# TIA_sep_amp_7_March.net
KiCad netlist of a schematic drawn in EAGLE
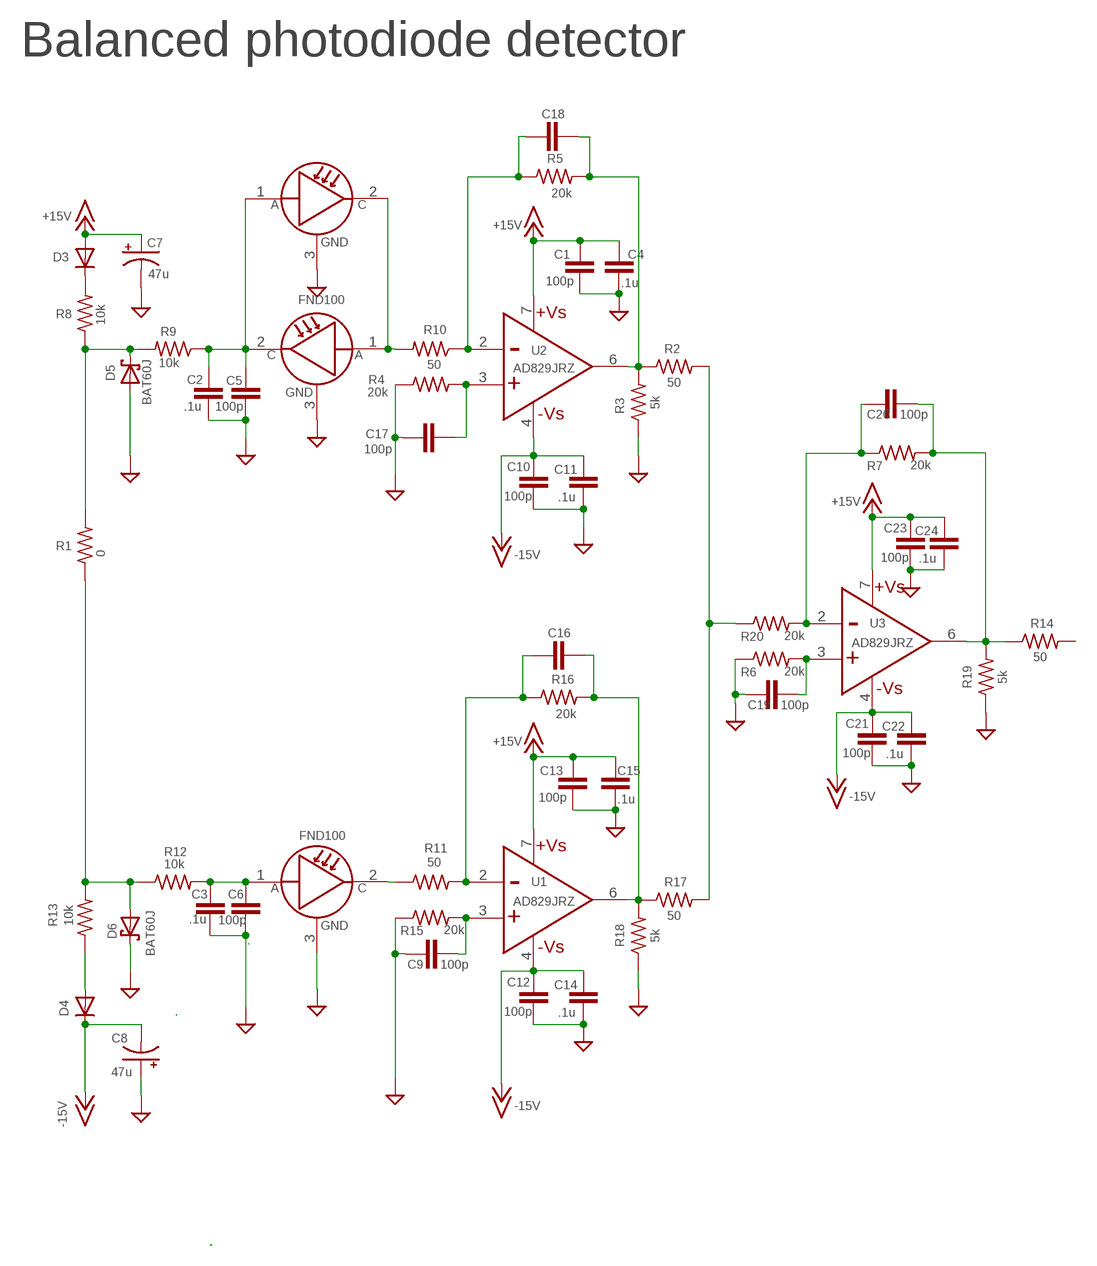
[diagram p0: schematic, sheet 1]

(export (version "E")
  (design (tool "Eeschema 10.0.6"))
  (components
    (comp (ref "C1")
      (value "100p")
      (footprint "eagle-import:C0603")
      (libsource (lib "eagle-import") (part "C-EUC0603"))
    )
    (comp (ref "C2")
      (value ".1u")
      (footprint "eagle-import:C0603")
      (libsource (lib "eagle-import") (part "C-EUC0603"))
    )
    (comp (ref "C3")
      (value ".1u")
      (footprint "eagle-import:C0603")
      (libsource (lib "eagle-import") (part "C-EUC0603"))
    )
    (comp (ref "C4")
      (value ".1u")
      (footprint "eagle-import:C0603")
      (libsource (lib "eagle-import") (part "C-EUC0603"))
    )
    (comp (ref "C5")
      (value "100p")
      (footprint "eagle-import:C0603")
      (libsource (lib "eagle-import") (part "C-EUC0603"))
    )
    (comp (ref "C6")
      (value "100p")
      (footprint "eagle-import:C0603")
      (libsource (lib "eagle-import") (part "C-EUC0603"))
    )
    (comp (ref "C7")
      (value "47u")
      (footprint "eagle-import:ETR3")
      (libsource (lib "eagle-import") (part "CPOL-USETR3"))
    )
    (comp (ref "C8")
      (value "47u")
      (footprint "eagle-import:ETR3")
      (libsource (lib "eagle-import") (part "CPOL-USETR3"))
    )
    (comp (ref "C9")
      (value "100p")
      (footprint "eagle-import:C0603")
      (libsource (lib "eagle-import") (part "C-EUC0603"))
    )
    (comp (ref "C10")
      (value "100p")
      (footprint "eagle-import:C0603")
      (libsource (lib "eagle-import") (part "C-EUC0603"))
    )
    (comp (ref "C11")
      (value ".1u")
      (footprint "eagle-import:C0603")
      (libsource (lib "eagle-import") (part "C-EUC0603"))
    )
    (comp (ref "C12")
      (value "100p")
      (footprint "eagle-import:C0603")
      (libsource (lib "eagle-import") (part "C-EUC0603"))
    )
    (comp (ref "C13")
      (value "100p")
      (footprint "eagle-import:C0603")
      (libsource (lib "eagle-import") (part "C-EUC0603"))
    )
    (comp (ref "C14")
      (value ".1u")
      (footprint "eagle-import:C0603")
      (libsource (lib "eagle-import") (part "C-EUC0603"))
    )
    (comp (ref "C15")
      (value ".1u")
      (footprint "eagle-import:C0603")
      (libsource (lib "eagle-import") (part "C-EUC0603"))
    )
    (comp (ref "C16")
      (value "C-EUC0603")
      (footprint "eagle-import:C0603")
      (libsource (lib "eagle-import") (part "C-EUC0603"))
    )
    (comp (ref "C17")
      (value "100p")
      (footprint "eagle-import:C0603")
      (libsource (lib "eagle-import") (part "C-EUC0603"))
    )
    (comp (ref "C18")
      (value "C-EUC0603")
      (footprint "eagle-import:C0603")
      (libsource (lib "eagle-import") (part "C-EUC0603"))
    )
    (comp (ref "C19")
      (value "100p")
      (footprint "eagle-import:C0603")
      (libsource (lib "eagle-import") (part "C-EUC0603"))
    )
    (comp (ref "C20")
      (value "100p")
      (footprint "eagle-import:C0603")
      (libsource (lib "eagle-import") (part "C-EUC0603"))
    )
    (comp (ref "C21")
      (value "100p")
      (footprint "eagle-import:C0603")
      (libsource (lib "eagle-import") (part "C-EUC0603"))
    )
    (comp (ref "C22")
      (value ".1u")
      (footprint "eagle-import:C0603")
      (libsource (lib "eagle-import") (part "C-EUC0603"))
    )
    (comp (ref "C23")
      (value "100p")
      (footprint "eagle-import:C0603")
      (libsource (lib "eagle-import") (part "C-EUC0603"))
    )
    (comp (ref "C24")
      (value ".1u")
      (footprint "eagle-import:C0603")
      (libsource (lib "eagle-import") (part "C-EUC0603"))
    )
    (comp (ref "D3")
      (value "SOD523DIODE")
      (footprint "eagle-import:SOD523")
      (libsource (lib "eagle-import") (part "SOD523DIODE"))
    )
    (comp (ref "D4")
      (value "SOD523DIODE")
      (footprint "eagle-import:SOD523")
      (libsource (lib "eagle-import") (part "SOD523DIODE"))
    )
    (comp (ref "D5")
      (value "BAT60J")
      (footprint "eagle-import:SOD323_ST")
      (libsource (lib "eagle-import") (part "BAT60J"))
    )
    (comp (ref "D6")
      (value "BAT60J")
      (footprint "eagle-import:SOD323_ST")
      (libsource (lib "eagle-import") (part "BAT60J"))
    )
    (comp (ref "R1")
      (value "0")
      (footprint "eagle-import:R0603")
      (libsource (lib "eagle-import") (part "R-US_R0603"))
    )
    (comp (ref "R2")
      (value "50")
      (footprint "eagle-import:R0603")
      (libsource (lib "eagle-import") (part "R-US_R0603"))
    )
    (comp (ref "R3")
      (value "5k")
      (footprint "eagle-import:R0603")
      (libsource (lib "eagle-import") (part "R-US_R0603"))
    )
    (comp (ref "R4")
      (value "20k")
      (footprint "eagle-import:R0603")
      (libsource (lib "eagle-import") (part "R-US_R0603"))
    )
    (comp (ref "R5")
      (value "20k")
      (footprint "eagle-import:R0603")
      (libsource (lib "eagle-import") (part "R-US_R0603"))
    )
    (comp (ref "R6")
      (value "20k")
      (footprint "eagle-import:R0603")
      (libsource (lib "eagle-import") (part "R-US_R0603"))
    )
    (comp (ref "R7")
      (value "20k")
      (footprint "eagle-import:R0603")
      (libsource (lib "eagle-import") (part "R-US_R0603"))
    )
    (comp (ref "R8")
      (value "10k")
      (footprint "eagle-import:R0603")
      (libsource (lib "eagle-import") (part "R-US_R0603"))
    )
    (comp (ref "R9")
      (value "10k")
      (footprint "eagle-import:R0603")
      (libsource (lib "eagle-import") (part "R-US_R0603"))
    )
    (comp (ref "R10")
      (value "50")
      (footprint "eagle-import:R0603")
      (libsource (lib "eagle-import") (part "R-US_R0603"))
    )
    (comp (ref "R11")
      (value "50")
      (footprint "eagle-import:R0603")
      (libsource (lib "eagle-import") (part "R-US_R0603"))
    )
    (comp (ref "R12")
      (value "10k")
      (footprint "eagle-import:R0603")
      (libsource (lib "eagle-import") (part "R-US_R0603"))
    )
    (comp (ref "R13")
      (value "10k")
      (footprint "eagle-import:R0603")
      (libsource (lib "eagle-import") (part "R-US_R0603"))
    )
    (comp (ref "R14")
      (value "50")
      (footprint "eagle-import:R0603")
      (libsource (lib "eagle-import") (part "R-US_R0603"))
    )
    (comp (ref "R15")
      (value "20k")
      (footprint "eagle-import:R0603")
      (libsource (lib "eagle-import") (part "R-US_R0603"))
    )
    (comp (ref "R16")
      (value "20k")
      (footprint "eagle-import:R0603")
      (libsource (lib "eagle-import") (part "R-US_R0603"))
    )
    (comp (ref "R17")
      (value "50")
      (footprint "eagle-import:R0603")
      (libsource (lib "eagle-import") (part "R-US_R0603"))
    )
    (comp (ref "R18")
      (value "5k")
      (footprint "eagle-import:R0603")
      (libsource (lib "eagle-import") (part "R-US_R0603"))
    )
    (comp (ref "R19")
      (value "5k")
      (footprint "eagle-import:R0603")
      (libsource (lib "eagle-import") (part "R-US_R0603"))
    )
    (comp (ref "R20")
      (value "20k")
      (footprint "eagle-import:R0603")
      (libsource (lib "eagle-import") (part "R-US_R0603"))
    )
    (comp (ref "U$1")
      (value "FND100")
      (footprint "eagle-import:TO254P939X470-3P")
      (libsource (lib "eagle-import") (part "FND100"))
    )
    (comp (ref "U$2")
      (value "FND100")
      (footprint "eagle-import:TO254P939X470-3P")
      (libsource (lib "eagle-import") (part "FND100"))
    )
    (comp (ref "U$4")
      (value "FND100")
      (footprint "eagle-import:TO254P939X470-3P")
      (libsource (lib "eagle-import") (part "FND100"))
    )
    (comp (ref "U1")
      (value "AD829JRZ")
      (footprint "eagle-import:SOIC127P600X175-8N")
      (libsource (lib "eagle-import") (part "AD829JRZ"))
    )
    (comp (ref "U2")
      (value "AD829JRZ")
      (footprint "eagle-import:SOIC127P600X175-8N")
      (libsource (lib "eagle-import") (part "AD829JRZ"))
    )
    (comp (ref "U3")
      (value "AD829JRZ")
      (footprint "eagle-import:SOIC127P600X175-8N")
      (libsource (lib "eagle-import") (part "AD829JRZ"))
    )
  )
  (nets
    (net (code "1") (name "+15V") (class "Default")
      (node (ref "C1") (pin "2") (pinfunction "2_2") (pintype "passive"))
      (node (ref "C13") (pin "2") (pinfunction "2_2") (pintype "passive"))
      (node (ref "C15") (pin "2") (pinfunction "2_2") (pintype "passive"))
      (node (ref "C23") (pin "2") (pinfunction "2_2") (pintype "passive"))
      (node (ref "C24") (pin "2") (pinfunction "2_2") (pintype "passive"))
      (node (ref "C4") (pin "2") (pinfunction "2_2") (pintype "passive"))
      (node (ref "C7") (pin "+") (pinfunction "+_+") (pintype "passive"))
      (node (ref "D3") (pin "A") (pinfunction "A_A") (pintype "passive"))
      (node (ref "U1") (pin "7") (pinfunction "+VS_7") (pintype "power_in"))
      (node (ref "U2") (pin "7") (pinfunction "+VS_7") (pintype "power_in"))
      (node (ref "U3") (pin "7") (pinfunction "+VS_7") (pintype "power_in"))
    )
    (net (code "2") (name "-15V") (class "Default")
      (node (ref "C10") (pin "2") (pinfunction "2_2") (pintype "passive"))
      (node (ref "C11") (pin "2") (pinfunction "2_2") (pintype "passive"))
      (node (ref "C12") (pin "2") (pinfunction "2_2") (pintype "passive"))
      (node (ref "C14") (pin "2") (pinfunction "2_2") (pintype "passive"))
      (node (ref "C21") (pin "2") (pinfunction "2_2") (pintype "passive"))
      (node (ref "C22") (pin "2") (pinfunction "2_2") (pintype "passive"))
      (node (ref "C8") (pin "-") (pinfunction "-_-") (pintype "passive"))
      (node (ref "D4") (pin "C") (pinfunction "C_C") (pintype "passive"))
      (node (ref "U1") (pin "4") (pinfunction "-VS_4") (pintype "power_in"))
      (node (ref "U2") (pin "4") (pinfunction "-VS_4") (pintype "power_in"))
      (node (ref "U3") (pin "4") (pinfunction "-VS_4") (pintype "power_in"))
    )
    (net (code "3") (name "GND") (class "Default")
      (node (ref "C1") (pin "1") (pinfunction "1_1") (pintype "passive"))
      (node (ref "C10") (pin "1") (pinfunction "1_1") (pintype "passive"))
      (node (ref "C11") (pin "1") (pinfunction "1_1") (pintype "passive"))
      (node (ref "C12") (pin "1") (pinfunction "1_1") (pintype "passive"))
      (node (ref "C13") (pin "1") (pinfunction "1_1") (pintype "passive"))
      (node (ref "C14") (pin "1") (pinfunction "1_1") (pintype "passive"))
      (node (ref "C15") (pin "1") (pinfunction "1_1") (pintype "passive"))
      (node (ref "C17") (pin "1") (pinfunction "1_1") (pintype "passive"))
      (node (ref "C19") (pin "1") (pinfunction "1_1") (pintype "passive"))
      (node (ref "C2") (pin "1") (pinfunction "1_1") (pintype "passive"))
      (node (ref "C21") (pin "1") (pinfunction "1_1") (pintype "passive"))
      (node (ref "C22") (pin "1") (pinfunction "1_1") (pintype "passive"))
      (node (ref "C23") (pin "1") (pinfunction "1_1") (pintype "passive"))
      (node (ref "C24") (pin "1") (pinfunction "1_1") (pintype "passive"))
      (node (ref "C3") (pin "1") (pinfunction "1_1") (pintype "passive"))
      (node (ref "C4") (pin "1") (pinfunction "1_1") (pintype "passive"))
      (node (ref "C5") (pin "1") (pinfunction "1_1") (pintype "passive"))
      (node (ref "C6") (pin "1") (pinfunction "1_1") (pintype "passive"))
      (node (ref "C7") (pin "-") (pinfunction "-_-") (pintype "passive"))
      (node (ref "C8") (pin "+") (pinfunction "+_+") (pintype "passive"))
      (node (ref "C9") (pin "1") (pinfunction "1_1") (pintype "passive"))
      (node (ref "D5") (pin "A") (pinfunction "A_A") (pintype "passive"))
      (node (ref "D6") (pin "C") (pinfunction "C_C") (pintype "passive"))
      (node (ref "R15") (pin "1") (pinfunction "1_1") (pintype "passive"))
      (node (ref "R18") (pin "1") (pinfunction "1_1") (pintype "passive"))
      (node (ref "R19") (pin "1") (pinfunction "1_1") (pintype "passive"))
      (node (ref "R3") (pin "1") (pinfunction "1_1") (pintype "passive"))
      (node (ref "R4") (pin "1") (pinfunction "1_1") (pintype "passive"))
      (node (ref "R6") (pin "1") (pinfunction "1_1") (pintype "passive"))
      (node (ref "U$1") (pin "3") (pinfunction "GND_3") (pintype "bidirectional"))
      (node (ref "U$2") (pin "3") (pinfunction "GND_3") (pintype "bidirectional"))
      (node (ref "U$4") (pin "3") (pinfunction "GND_3") (pintype "bidirectional"))
    )
    (net (code "4") (name "Net-(D3-PadC)") (class "Default")
      (node (ref "D3") (pin "C") (pinfunction "C_C") (pintype "passive"))
      (node (ref "R8") (pin "2") (pinfunction "2_2") (pintype "passive"))
    )
    (net (code "5") (name "Net-(D4-PadA)") (class "Default")
      (node (ref "D4") (pin "A") (pinfunction "A_A") (pintype "passive"))
      (node (ref "R13") (pin "1") (pinfunction "1_1") (pintype "passive"))
    )
    (net (code "6") (name "Net-(D5-PadC)") (class "Default")
      (node (ref "D5") (pin "C") (pinfunction "C_C") (pintype "passive"))
      (node (ref "R1") (pin "2") (pinfunction "2_2") (pintype "passive"))
      (node (ref "R8") (pin "1") (pinfunction "1_1") (pintype "passive"))
      (node (ref "R9") (pin "2") (pinfunction "2_2") (pintype "passive"))
    )
    (net (code "7") (name "Net-(D6-PadA)") (class "Default")
      (node (ref "D6") (pin "A") (pinfunction "A_A") (pintype "passive"))
      (node (ref "R1") (pin "1") (pinfunction "1_1") (pintype "passive"))
      (node (ref "R12") (pin "1") (pinfunction "1_1") (pintype "passive"))
      (node (ref "R13") (pin "2") (pinfunction "2_2") (pintype "passive"))
    )
    (net (code "8") (name "Net-(R17-Pad2)") (class "Default")
      (node (ref "R17") (pin "2") (pinfunction "2_2") (pintype "passive"))
      (node (ref "R2") (pin "2") (pinfunction "2_2") (pintype "passive"))
      (node (ref "R20") (pin "1") (pinfunction "1_1") (pintype "passive"))
    )
    (net (code "9") (name "Net-(U$1-A)") (class "Default")
      (node (ref "R10") (pin "2") (pinfunction "2_2") (pintype "passive"))
      (node (ref "U$1") (pin "1") (pinfunction "A_1") (pintype "bidirectional"))
      (node (ref "U$4") (pin "2") (pinfunction "C_2") (pintype "bidirectional"))
    )
    (net (code "10") (name "Net-(U$1-C)") (class "Default")
      (node (ref "C2") (pin "2") (pinfunction "2_2") (pintype "passive"))
      (node (ref "C5") (pin "2") (pinfunction "2_2") (pintype "passive"))
      (node (ref "R9") (pin "1") (pinfunction "1_1") (pintype "passive"))
      (node (ref "U$1") (pin "2") (pinfunction "C_2") (pintype "bidirectional"))
      (node (ref "U$4") (pin "1") (pinfunction "A_1") (pintype "bidirectional"))
    )
    (net (code "11") (name "Net-(U$2-A)") (class "Default")
      (node (ref "C3") (pin "2") (pinfunction "2_2") (pintype "passive"))
      (node (ref "C6") (pin "2") (pinfunction "2_2") (pintype "passive"))
      (node (ref "R12") (pin "2") (pinfunction "2_2") (pintype "passive"))
      (node (ref "U$2") (pin "1") (pinfunction "A_1") (pintype "bidirectional"))
    )
    (net (code "12") (name "Net-(U$2-C)") (class "Default")
      (node (ref "R11") (pin "1") (pinfunction "1_1") (pintype "passive"))
      (node (ref "U$2") (pin "2") (pinfunction "C_2") (pintype "bidirectional"))
    )
    (net (code "13") (name "Net-(U1-+IN)") (class "Default")
      (node (ref "C9") (pin "2") (pinfunction "2_2") (pintype "passive"))
      (node (ref "R15") (pin "2") (pinfunction "2_2") (pintype "passive"))
      (node (ref "U1") (pin "3") (pinfunction "+IN_3") (pintype "input"))
    )
    (net (code "14") (name "Net-(U1--IN)") (class "Default")
      (node (ref "C16") (pin "1") (pinfunction "1_1") (pintype "passive"))
      (node (ref "R11") (pin "2") (pinfunction "2_2") (pintype "passive"))
      (node (ref "R16") (pin "1") (pinfunction "1_1") (pintype "passive"))
      (node (ref "U1") (pin "2") (pinfunction "-IN_2") (pintype "input"))
    )
    (net (code "15") (name "Net-(U1-OUTPUT)") (class "Default")
      (node (ref "C16") (pin "2") (pinfunction "2_2") (pintype "passive"))
      (node (ref "R16") (pin "2") (pinfunction "2_2") (pintype "passive"))
      (node (ref "R17") (pin "1") (pinfunction "1_1") (pintype "passive"))
      (node (ref "R18") (pin "2") (pinfunction "2_2") (pintype "passive"))
      (node (ref "U1") (pin "6") (pinfunction "OUTPUT_6") (pintype "output"))
    )
    (net (code "16") (name "Net-(U2-+IN)") (class "Default")
      (node (ref "C17") (pin "2") (pinfunction "2_2") (pintype "passive"))
      (node (ref "R4") (pin "2") (pinfunction "2_2") (pintype "passive"))
      (node (ref "U2") (pin "3") (pinfunction "+IN_3") (pintype "input"))
    )
    (net (code "17") (name "Net-(U2--IN)") (class "Default")
      (node (ref "C18") (pin "1") (pinfunction "1_1") (pintype "passive"))
      (node (ref "R10") (pin "1") (pinfunction "1_1") (pintype "passive"))
      (node (ref "R5") (pin "1") (pinfunction "1_1") (pintype "passive"))
      (node (ref "U2") (pin "2") (pinfunction "-IN_2") (pintype "input"))
    )
    (net (code "18") (name "Net-(U2-OUTPUT)") (class "Default")
      (node (ref "C18") (pin "2") (pinfunction "2_2") (pintype "passive"))
      (node (ref "R2") (pin "1") (pinfunction "1_1") (pintype "passive"))
      (node (ref "R3") (pin "2") (pinfunction "2_2") (pintype "passive"))
      (node (ref "R5") (pin "2") (pinfunction "2_2") (pintype "passive"))
      (node (ref "U2") (pin "6") (pinfunction "OUTPUT_6") (pintype "output"))
    )
    (net (code "19") (name "Net-(U3-+IN)") (class "Default")
      (node (ref "C19") (pin "2") (pinfunction "2_2") (pintype "passive"))
      (node (ref "R6") (pin "2") (pinfunction "2_2") (pintype "passive"))
      (node (ref "U3") (pin "3") (pinfunction "+IN_3") (pintype "input"))
    )
    (net (code "20") (name "Net-(U3--IN)") (class "Default")
      (node (ref "C20") (pin "1") (pinfunction "1_1") (pintype "passive"))
      (node (ref "R20") (pin "2") (pinfunction "2_2") (pintype "passive"))
      (node (ref "R7") (pin "1") (pinfunction "1_1") (pintype "passive"))
      (node (ref "U3") (pin "2") (pinfunction "-IN_2") (pintype "input"))
    )
    (net (code "21") (name "Net-(U3-OUTPUT)") (class "Default")
      (node (ref "C20") (pin "2") (pinfunction "2_2") (pintype "passive"))
      (node (ref "R14") (pin "1") (pinfunction "1_1") (pintype "passive"))
      (node (ref "R19") (pin "2") (pinfunction "2_2") (pintype "passive"))
      (node (ref "R7") (pin "2") (pinfunction "2_2") (pintype "passive"))
      (node (ref "U3") (pin "6") (pinfunction "OUTPUT_6") (pintype "output"))
    )
    (net (code "22") (name "unconnected-(R14-Pad2)") (class "Default")
      (node (ref "R14") (pin "2") (pinfunction "2_2") (pintype "passive"))
    )
  )
)
